# main.net
KiCad netlist of a schematic drawn in Altium Designer
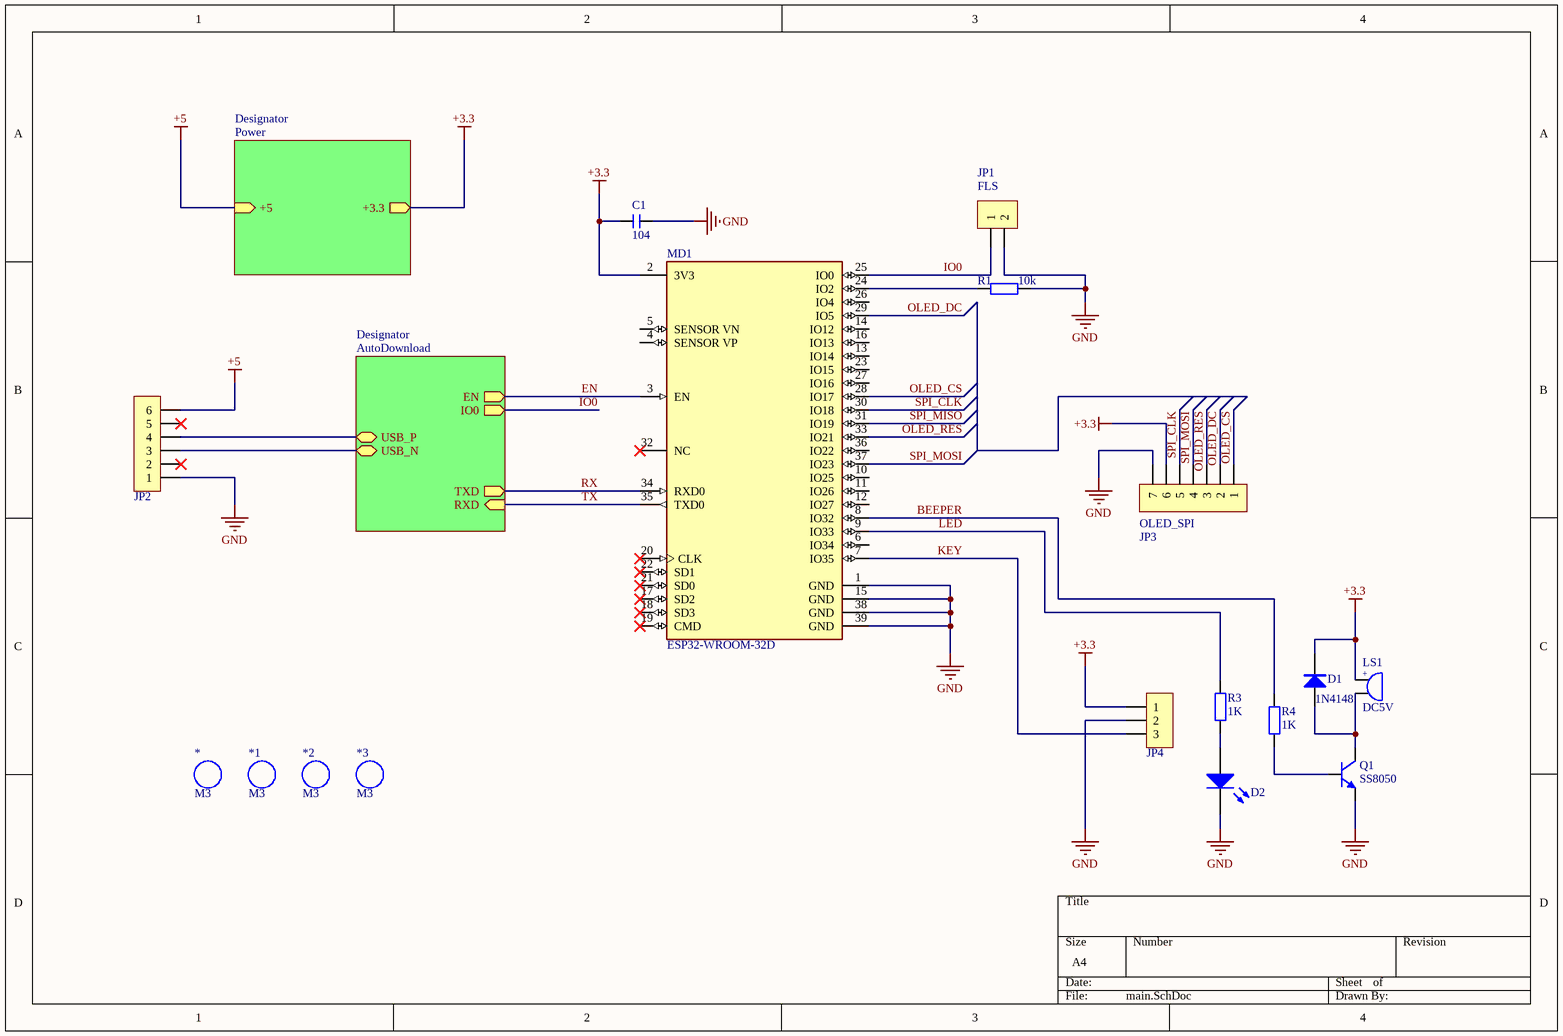
[diagram p0: main.SchDoc]

(export (version "E")
  (design (tool "Eeschema 10.0.6"))
  (components
    (comp (ref "*")
      (value "M3")
      (footprint "M3 125X200")
      (description "铜柱孔")
      (libsource (lib "0.7 - 常用按键-开关-蜂鸣器-电池") (part "M3"))
    )
    (comp (ref "*1")
      (value "M3")
      (footprint "M3 125X200")
      (description "铜柱孔")
      (libsource (lib "0.7 - 常用按键-开关-蜂鸣器-电池") (part "M3"))
    )
    (comp (ref "*2")
      (value "M3")
      (footprint "M3 125X200")
      (description "铜柱孔")
      (libsource (lib "0.7 - 常用按键-开关-蜂鸣器-电池") (part "M3"))
    )
    (comp (ref "*3")
      (value "M3")
      (footprint "M3 125X200")
      (description "铜柱孔")
      (libsource (lib "0.7 - 常用按键-开关-蜂鸣器-电池") (part "M3"))
    )
    (comp (ref "C1")
      (value "104")
      (footprint "C 0603-L")
      (description "贴片电容")
      (libsource (lib "0.1 - 电阻-电容-电感") (part "C"))
    )
    (comp (ref "D1")
      (value "1N4148")
      (footprint "MINI_MELF (LL34)")
      (description "开关二极管")
      (libsource (lib "0.2 - 二极管-整流桥") (part "1N4148"))
    )
    (comp (ref "D2")
      (value "LED")
      (footprint "LED 0603R")
      (description "发光二极管")
      (libsource (lib "0.3 - LED发光二极管") (part "LED"))
    )
    (comp (ref "JP1")
      (value "FLS")
      (footprint "HDR1.27-LI-2P")
      (description "2P接插件")
      (libsource (lib "5.1 - 接插件-脚距1.27") (part "Header 2"))
    )
    (comp (ref "JP2")
      (value "HDR-1X6")
      (footprint "XH2.54-LI-6P")
      (description "6P接插件")
      (libsource (lib "5.4 - 接插件-脚距2.54 (100mil) ") (part "Header 6"))
    )
    (comp (ref "JP3")
      (value "OLED_SPI")
      (footprint "HDR2.54-M-LI-7P")
      (description "7P接插件")
      (libsource (lib "5.4 - 接插件-脚距2.54 (100mil) ") (part "Header 7"))
    )
    (comp (ref "JP4")
      (value "HDR-1X3")
      (footprint "XH2.54-LI-3P")
      (description "3P接插件")
      (libsource (lib "5.4 - 接插件-脚距2.54 (100mil) ") (part "Header 3"))
    )
    (comp (ref "LS1")
      (value "DC5V")
      (footprint "BEEP 5x9x5.5")
      (description "蜂鸣器")
      (libsource (lib "0.7 - 常用按键-开关-蜂鸣器-电池") (part "BEEP"))
    )
    (comp (ref "MD1")
      (value "ESP32-WROOM-32D")
      (footprint "FP-ESP32-WROOM-32D-MFG")
      (description "WIFI MODULE 32MBITS SPI FLASH")
      (fields
        (field (name "OCTOPART") "https://octopart.com/esp32-wroom-32d-espressif+systems-91040050")
        (field (name "MANUFACTURER") "Espressif Systems")
      )
      (libsource (lib "Altium Content Vault") (part "a031a76f8c27026a7a7f4657ff233a3"))
    )
    (comp (ref "Q1")
      (value "SS8050")
      (footprint "SOT23-3N")
      (description "高频放大-NPN型")
      (libsource (lib "0.4 - 三极管-场效应管-可控硅") (part "8050-SMD"))
    )
    (comp (ref "R1")
      (value "10k")
      (footprint "R 0603_L")
      (description "贴片电阻")
      (libsource (lib "0.1 - 电阻-电容-电感") (part "R"))
    )
    (comp (ref "R3")
      (value "1K")
      (footprint "R 0603_L")
      (description "贴片电阻")
      (libsource (lib "0.1 - 电阻-电容-电感") (part "R"))
    )
    (comp (ref "R4")
      (value "1K")
      (footprint "R 0603_L")
      (description "贴片电阻")
      (libsource (lib "0.1 - 电阻-电容-电感") (part "R"))
    )
  )
  (nets
    (net (code "1") (name "+3.3") (class "Default")
      (node (ref "C1") (pin "1") (pinfunction "1_1") (pintype "passive"))
      (node (ref "D1") (pin "2") (pinfunction "K_2") (pintype "passive"))
      (node (ref "JP3") (pin "6") (pinfunction "6_6") (pintype "passive"))
      (node (ref "JP4") (pin "1") (pinfunction "1_1") (pintype "passive"))
      (node (ref "LS1") (pin "1") (pinfunction "1_1") (pintype "passive"))
      (node (ref "MD1") (pin "2") (pinfunction "3V3_2") (pintype "power_in"))
    )
    (net (code "2") (name "+5") (class "Default")
      (node (ref "JP2") (pin "6") (pinfunction "6_6") (pintype "passive"))
    )
    (net (code "3") (name "/BEEPER") (class "Default")
      (node (ref "MD1") (pin "8") (pinfunction "IO32_8") (pintype "bidirectional"))
      (node (ref "R4") (pin "2") (pinfunction "2_2") (pintype "passive"))
    )
    (net (code "4") (name "/EN") (class "Default")
      (node (ref "MD1") (pin "3") (pinfunction "EN_3") (pintype "input"))
    )
    (net (code "5") (name "/IO0") (class "Default")
      (node (ref "JP1") (pin "1") (pinfunction "1_1") (pintype "passive"))
      (node (ref "MD1") (pin "25") (pinfunction "IO0_25") (pintype "bidirectional"))
    )
    (net (code "6") (name "/KEY") (class "Default")
      (node (ref "JP4") (pin "3") (pinfunction "3_3") (pintype "passive"))
      (node (ref "MD1") (pin "7") (pinfunction "IO35_7") (pintype "bidirectional"))
    )
    (net (code "7") (name "/LED") (class "Default")
      (node (ref "MD1") (pin "9") (pinfunction "IO33_9") (pintype "bidirectional"))
      (node (ref "R3") (pin "2") (pinfunction "2_2") (pintype "passive"))
    )
    (net (code "8") (name "/OLED_CS") (class "Default")
      (node (ref "JP3") (pin "1") (pinfunction "1_1") (pintype "passive"))
      (node (ref "MD1") (pin "28") (pinfunction "IO17_28") (pintype "bidirectional"))
    )
    (net (code "9") (name "/OLED_DC") (class "Default")
      (node (ref "JP3") (pin "2") (pinfunction "2_2") (pintype "passive"))
      (node (ref "MD1") (pin "29") (pinfunction "IO5_29") (pintype "bidirectional"))
    )
    (net (code "10") (name "/OLED_RES") (class "Default")
      (node (ref "JP3") (pin "3") (pinfunction "3_3") (pintype "passive"))
      (node (ref "MD1") (pin "33") (pinfunction "IO21_33") (pintype "bidirectional"))
    )
    (net (code "11") (name "/RX") (class "Default")
      (node (ref "MD1") (pin "34") (pinfunction "RXD0_34") (pintype "input"))
    )
    (net (code "12") (name "/SPI_CLK") (class "Default")
      (node (ref "JP3") (pin "5") (pinfunction "5_5") (pintype "passive"))
      (node (ref "MD1") (pin "30") (pinfunction "IO18_30") (pintype "bidirectional"))
    )
    (net (code "13") (name "/SPI_MISO") (class "Default")
      (node (ref "MD1") (pin "31") (pinfunction "IO19_31") (pintype "bidirectional"))
    )
    (net (code "14") (name "/SPI_MOSI") (class "Default")
      (node (ref "JP3") (pin "4") (pinfunction "4_4") (pintype "passive"))
      (node (ref "MD1") (pin "37") (pinfunction "IO23_37") (pintype "bidirectional"))
    )
    (net (code "15") (name "/TX") (class "Default")
      (node (ref "MD1") (pin "35") (pinfunction "TXD0_35") (pintype "output"))
    )
    (net (code "16") (name "/USB_N") (class "Default")
      (node (ref "JP2") (pin "3") (pinfunction "3_3") (pintype "passive"))
    )
    (net (code "17") (name "/USB_P") (class "Default")
      (node (ref "JP2") (pin "4") (pinfunction "4_4") (pintype "passive"))
    )
    (net (code "18") (name "GND") (class "Default")
      (node (ref "C1") (pin "2") (pinfunction "2_2") (pintype "passive"))
      (node (ref "D2") (pin "2") (pinfunction "K_2") (pintype "passive"))
      (node (ref "JP1") (pin "2") (pinfunction "2_2") (pintype "passive"))
      (node (ref "JP2") (pin "1") (pinfunction "1_1") (pintype "passive"))
      (node (ref "JP3") (pin "7") (pinfunction "7_7") (pintype "passive"))
      (node (ref "JP4") (pin "2") (pinfunction "2_2") (pintype "passive"))
      (node (ref "MD1") (pin "1") (pinfunction "GND_1") (pintype "power_in"))
      (node (ref "MD1") (pin "15") (pinfunction "GND_15") (pintype "power_in"))
      (node (ref "MD1") (pin "38") (pinfunction "GND_38") (pintype "power_in"))
      (node (ref "MD1") (pin "39") (pinfunction "GND_39") (pintype "power_in"))
      (node (ref "Q1") (pin "2") (pinfunction "E_2") (pintype "passive"))
      (node (ref "R1") (pin "2") (pinfunction "2_2") (pintype "passive"))
    )
    (net (code "19") (name "Net-(D1-A)") (class "Default")
      (node (ref "D1") (pin "1") (pinfunction "A_1") (pintype "passive"))
      (node (ref "LS1") (pin "2") (pinfunction "2_2") (pintype "passive"))
      (node (ref "Q1") (pin "3") (pinfunction "C_3") (pintype "passive"))
    )
    (net (code "20") (name "Net-(D2-A)") (class "Default")
      (node (ref "D2") (pin "1") (pinfunction "A_1") (pintype "passive"))
      (node (ref "R3") (pin "1") (pinfunction "1_1") (pintype "passive"))
    )
    (net (code "21") (name "Net-(MD1-IO2)") (class "Default")
      (node (ref "MD1") (pin "24") (pinfunction "IO2_24") (pintype "bidirectional"))
      (node (ref "R1") (pin "1") (pinfunction "1_1") (pintype "passive"))
    )
    (net (code "22") (name "Net-(Q1-B)") (class "Default")
      (node (ref "Q1") (pin "1") (pinfunction "B_1") (pintype "passive"))
      (node (ref "R4") (pin "1") (pinfunction "1_1") (pintype "passive"))
    )
    (net (code "23") (name "unconnected-(JP2-Pad2)") (class "Default")
      (node (ref "JP2") (pin "2") (pinfunction "2_2") (pintype "passive+no_connect"))
    )
    (net (code "24") (name "unconnected-(JP2-Pad5)") (class "Default")
      (node (ref "JP2") (pin "5") (pinfunction "5_5") (pintype "passive+no_connect"))
    )
    (net (code "25") (name "unconnected-(MD1-CLK-Pad20)") (class "Default")
      (node (ref "MD1") (pin "20") (pinfunction "CLK_20") (pintype "input+no_connect"))
    )
    (net (code "26") (name "unconnected-(MD1-CMD-Pad19)") (class "Default")
      (node (ref "MD1") (pin "19") (pinfunction "CMD_19") (pintype "bidirectional+no_connect"))
    )
    (net (code "27") (name "unconnected-(MD1-IO4-Pad26)") (class "Default")
      (node (ref "MD1") (pin "26") (pinfunction "IO4_26") (pintype "bidirectional"))
    )
    (net (code "28") (name "unconnected-(MD1-IO12-Pad14)") (class "Default")
      (node (ref "MD1") (pin "14") (pinfunction "IO12_14") (pintype "bidirectional"))
    )
    (net (code "29") (name "unconnected-(MD1-IO13-Pad16)") (class "Default")
      (node (ref "MD1") (pin "16") (pinfunction "IO13_16") (pintype "bidirectional"))
    )
    (net (code "30") (name "unconnected-(MD1-IO14-Pad13)") (class "Default")
      (node (ref "MD1") (pin "13") (pinfunction "IO14_13") (pintype "bidirectional"))
    )
    (net (code "31") (name "unconnected-(MD1-IO15-Pad23)") (class "Default")
      (node (ref "MD1") (pin "23") (pinfunction "IO15_23") (pintype "bidirectional"))
    )
    (net (code "32") (name "unconnected-(MD1-IO16-Pad27)") (class "Default")
      (node (ref "MD1") (pin "27") (pinfunction "IO16_27") (pintype "bidirectional"))
    )
    (net (code "33") (name "unconnected-(MD1-IO22-Pad36)") (class "Default")
      (node (ref "MD1") (pin "36") (pinfunction "IO22_36") (pintype "bidirectional"))
    )
    (net (code "34") (name "unconnected-(MD1-IO25-Pad10)") (class "Default")
      (node (ref "MD1") (pin "10") (pinfunction "IO25_10") (pintype "bidirectional"))
    )
    (net (code "35") (name "unconnected-(MD1-IO26-Pad11)") (class "Default")
      (node (ref "MD1") (pin "11") (pinfunction "IO26_11") (pintype "bidirectional"))
    )
    (net (code "36") (name "unconnected-(MD1-IO27-Pad12)") (class "Default")
      (node (ref "MD1") (pin "12") (pinfunction "IO27_12") (pintype "bidirectional"))
    )
    (net (code "37") (name "unconnected-(MD1-IO34-Pad6)") (class "Default")
      (node (ref "MD1") (pin "6") (pinfunction "IO34_6") (pintype "bidirectional"))
    )
    (net (code "38") (name "unconnected-(MD1-NC-Pad32)") (class "Default")
      (node (ref "MD1") (pin "32") (pinfunction "NC_32") (pintype "passive+no_connect"))
    )
    (net (code "39") (name "unconnected-(MD1-SD0-Pad21)") (class "Default")
      (node (ref "MD1") (pin "21") (pinfunction "SD0_21") (pintype "bidirectional+no_connect"))
    )
    (net (code "40") (name "unconnected-(MD1-SD1-Pad22)") (class "Default")
      (node (ref "MD1") (pin "22") (pinfunction "SD1_22") (pintype "bidirectional+no_connect"))
    )
    (net (code "41") (name "unconnected-(MD1-SD2-Pad17)") (class "Default")
      (node (ref "MD1") (pin "17") (pinfunction "SD2_17") (pintype "bidirectional+no_connect"))
    )
    (net (code "42") (name "unconnected-(MD1-SD3-Pad18)") (class "Default")
      (node (ref "MD1") (pin "18") (pinfunction "SD3_18") (pintype "bidirectional+no_connect"))
    )
    (net (code "43") (name "unconnected-(MD1-SENSOR_VN-Pad5)") (class "Default")
      (node (ref "MD1") (pin "5") (pinfunction "SENSOR_VN_5") (pintype "bidirectional"))
    )
    (net (code "44") (name "unconnected-(MD1-SENSOR_VP-Pad4)") (class "Default")
      (node (ref "MD1") (pin "4") (pinfunction "SENSOR_VP_4") (pintype "bidirectional"))
    )
  )
)
